# Sheet2.net
KiCad netlist of a schematic drawn in Altium Designer
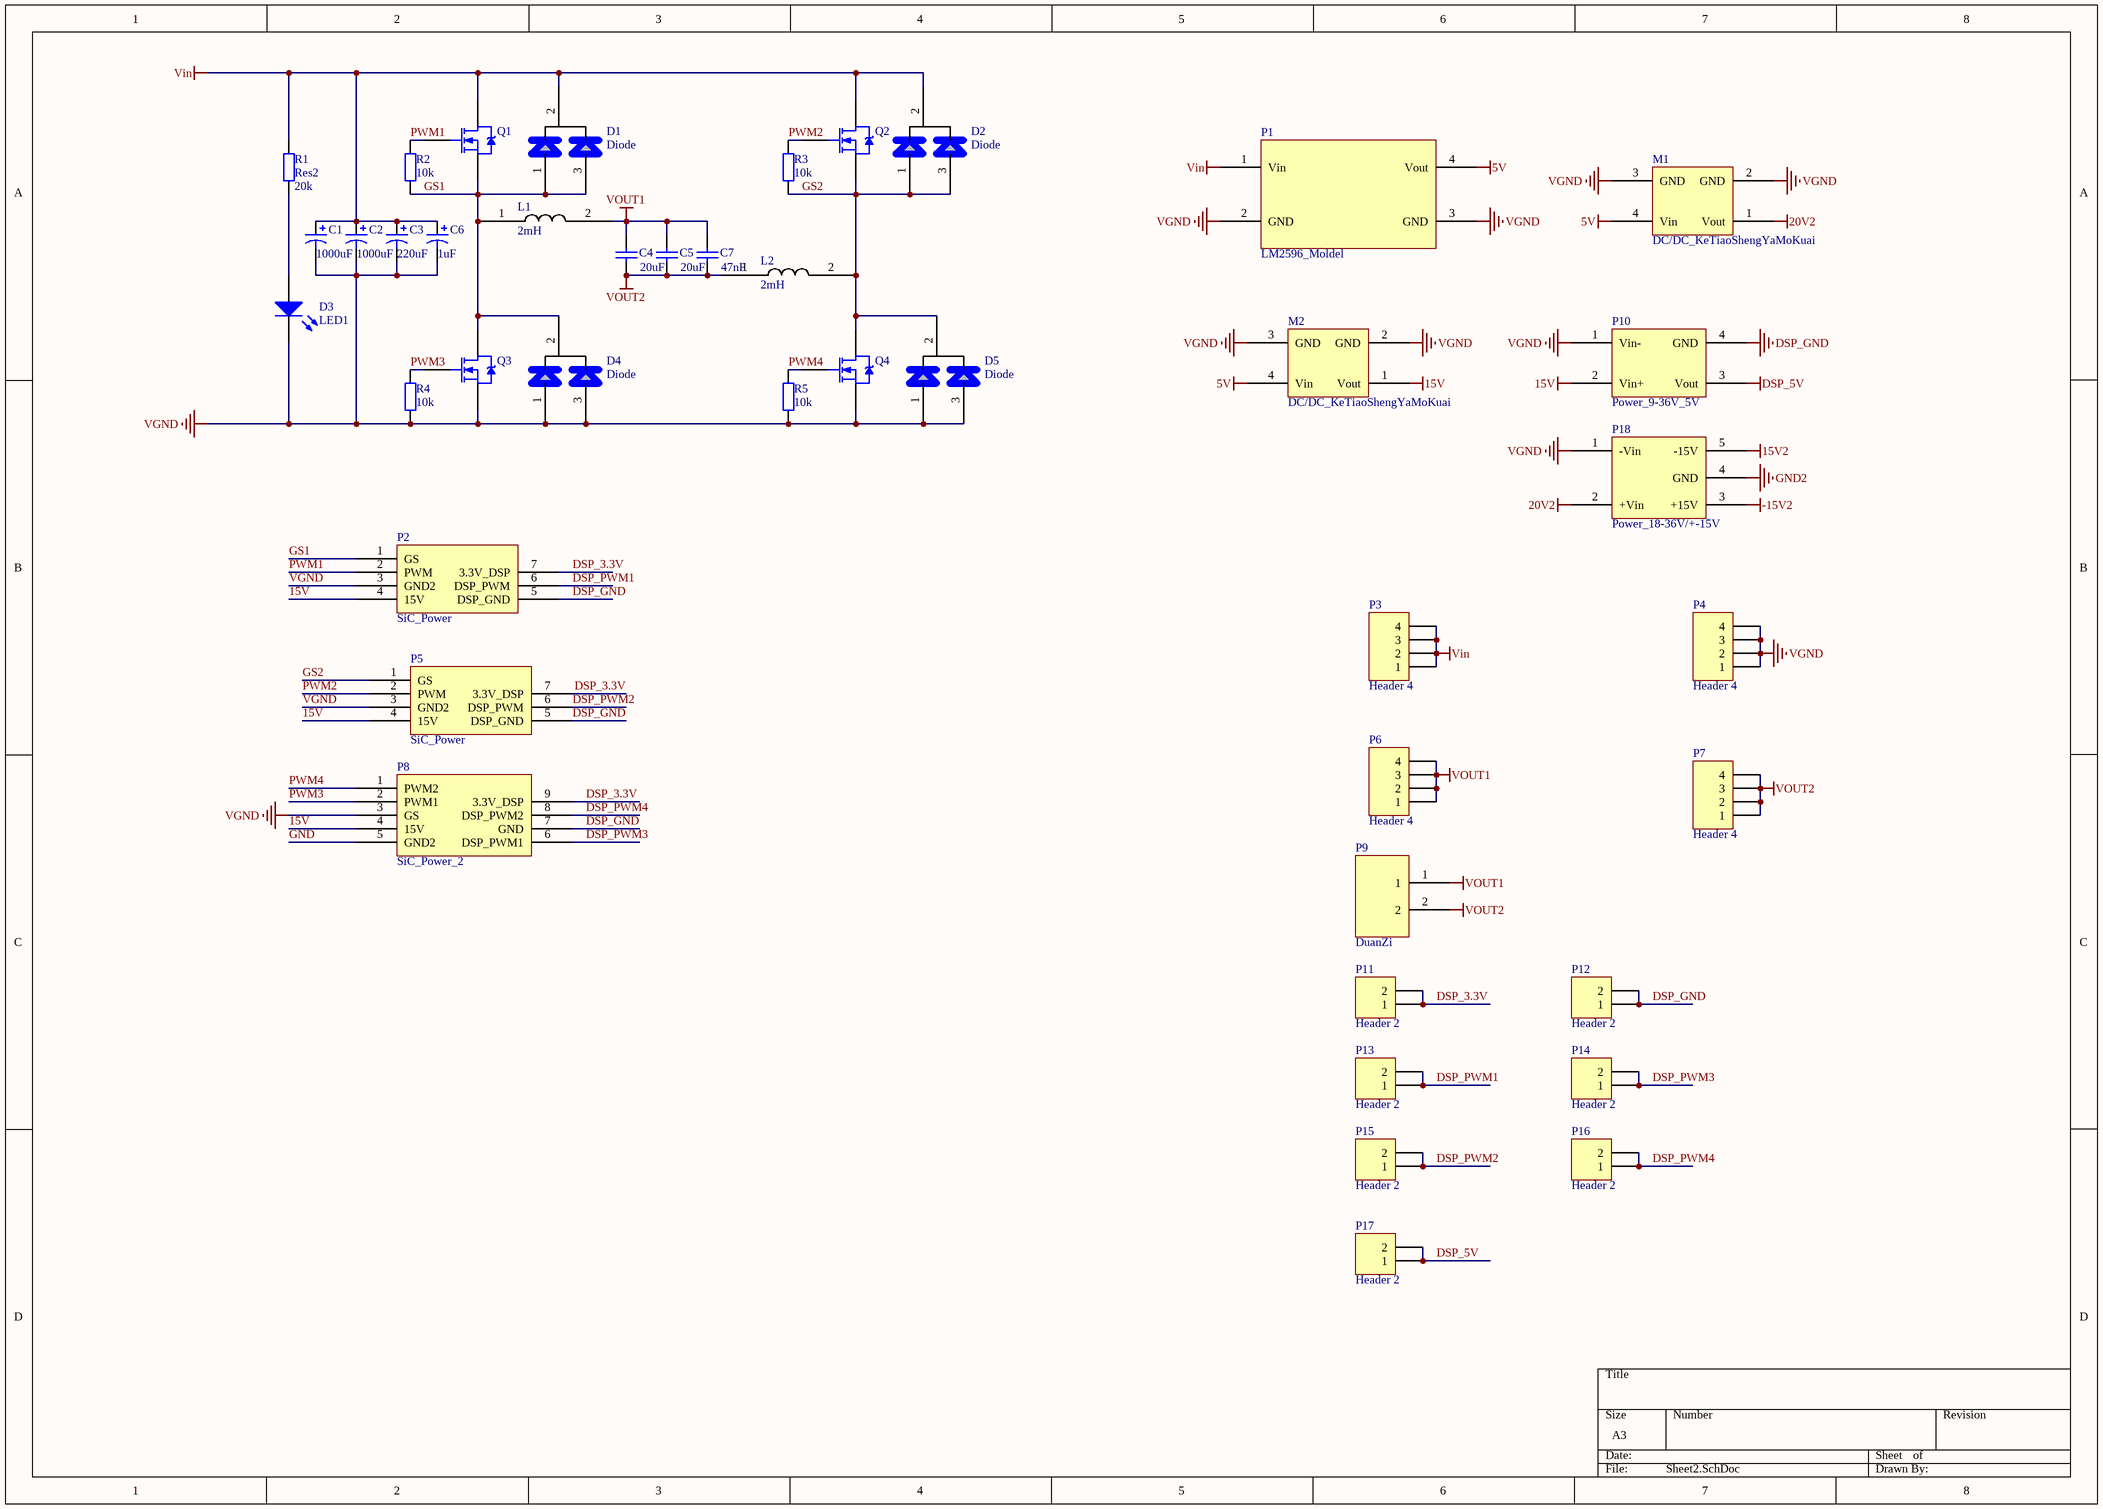
[diagram p0: Sheet2.SchDoc]

(export (version "E")
  (design (tool "Eeschema 10.0.6"))
  (components
    (comp (ref "C1")
      (value "1000uF")
      (footprint "C_1000uF_220uF")
      (description "Polarized Capacitor (Radial)")
      (fields (field (name "Comment") "Cap Pol1") (field (name "PUBLISHER") "Altium Limited"))
      (libsource (lib "Miscellaneous Devices") (part "Cap Pol1"))
    )
    (comp (ref "C2")
      (value "1000uF")
      (footprint "C_1000uF_220uF")
      (description "Polarized Capacitor (Radial)")
      (fields (field (name "Comment") "Cap Pol1") (field (name "PUBLISHER") "Altium Limited"))
      (libsource (lib "Miscellaneous Devices") (part "Cap Pol1"))
    )
    (comp (ref "C3")
      (value "220uF")
      (footprint "C_1000uF_220uF")
      (description "Polarized Capacitor (Radial)")
      (fields (field (name "Comment") "Cap Pol1") (field (name "PUBLISHER") "Altium Limited"))
      (libsource (lib "Miscellaneous Devices") (part "Cap Pol1"))
    )
    (comp (ref "C4")
      (value "20uF")
      (footprint "C_20uF_BaoMo")
      (description "Capacitor (Semiconductor SIM Model)")
      (fields (field (name "Comment") "Cap Semi") (field (name "PUBLISHER") "Altium Limited"))
      (libsource (lib "Miscellaneous Devices") (part "Cap Semi"))
    )
    (comp (ref "C5")
      (value "20uF")
      (footprint "C_20uF_BaoMo")
      (description "Capacitor (Semiconductor SIM Model)")
      (fields (field (name "Comment") "Cap Semi") (field (name "PUBLISHER") "Altium Limited"))
      (libsource (lib "Miscellaneous Devices") (part "Cap Semi"))
    )
    (comp (ref "C6")
      (value "1uF")
      (footprint "C_MKP_1uF")
      (description "Polarized Capacitor (Radial)")
      (fields (field (name "Comment") "Cap Pol1") (field (name "PUBLISHER") "Altium Limited"))
      (libsource (lib "Miscellaneous Devices") (part "Cap Pol1"))
    )
    (comp (ref "C7")
      (value "47nF")
      (footprint "C_0047_630_400_47nF")
      (description "Capacitor (Semiconductor SIM Model)")
      (fields (field (name "Comment") "Cap Semi") (field (name "PUBLISHER") "Altium Limited"))
      (libsource (lib "Miscellaneous Devices") (part "Cap Semi"))
    )
    (comp (ref "D1") (value "Diode") (footprint "SiC-MOS") (libsource (lib "sharing") (part "Diode")))
    (comp (ref "D2") (value "Diode") (footprint "SiC-MOS") (libsource (lib "sharing") (part "Diode")))
    (comp (ref "D3")
      (value "LED1")
      (footprint "LED")
      (description "Typical RED GaAs LED")
      (fields (field (name "PUBLISHER") "Altium Limited"))
      (libsource (lib "Miscellaneous Devices") (part "LED1"))
    )
    (comp (ref "D4") (value "Diode") (footprint "SiC-MOS") (libsource (lib "sharing") (part "Diode")))
    (comp (ref "D5") (value "Diode") (footprint "SiC-MOS") (libsource (lib "sharing") (part "Diode")))
    (comp (ref "L1") (value "2mH") (footprint "L_2mH") (libsource (lib "sharing") (part "L")))
    (comp (ref "L2") (value "2mH") (footprint "L_2mH") (libsource (lib "sharing") (part "L")))
    (comp (ref "M1")
      (value "DC/DC_KeTiaoShengYaMoKuai")
      (footprint "DC/DC-KeTiaoShengYaMoBan")
      (libsource (lib "sharing") (part "DC/DC_KeTiaoShengYaMoKuai"))
    )
    (comp (ref "M2")
      (value "DC/DC_KeTiaoShengYaMoKuai")
      (footprint "DC/DC-KeTiaoShengYaMoBan")
      (libsource (lib "sharing") (part "DC/DC_KeTiaoShengYaMoKuai"))
    )
    (comp (ref "P1")
      (value "LM2596_Moldel")
      (footprint "LM2596_Moldel")
      (libsource (lib "sharing") (part "LM2596_Moldel"))
    )
    (comp (ref "P2")
      (value "SiC_Power")
      (footprint "SiC_Power")
      (libsource (lib "sharing") (part "SiC_Power"))
    )
    (comp (ref "P3")
      (value "Header 4")
      (footprint "HDR1X4")
      (description "Header, 4-Pin")
      (fields (field (name "PUBLISHER") "Altium Limited"))
      (libsource (lib "Miscellaneous Connectors") (part "Header 4"))
    )
    (comp (ref "P4")
      (value "Header 4")
      (footprint "HDR1X4")
      (description "Header, 4-Pin")
      (fields (field (name "PUBLISHER") "Altium Limited"))
      (libsource (lib "Miscellaneous Connectors") (part "Header 4"))
    )
    (comp (ref "P5")
      (value "SiC_Power")
      (footprint "SiC_Power")
      (libsource (lib "sharing") (part "SiC_Power"))
    )
    (comp (ref "P6")
      (value "Header 4")
      (footprint "HDR1X4")
      (description "Header, 4-Pin")
      (fields (field (name "PUBLISHER") "Altium Limited"))
      (libsource (lib "Miscellaneous Connectors") (part "Header 4"))
    )
    (comp (ref "P7")
      (value "Header 4")
      (footprint "HDR1X4")
      (description "Header, 4-Pin")
      (fields (field (name "PUBLISHER") "Altium Limited"))
      (libsource (lib "Miscellaneous Connectors") (part "Header 4"))
    )
    (comp (ref "P8")
      (value "SiC_Power_2")
      (footprint "SiC_Power_2")
      (libsource (lib "sharing") (part "SiC_Power_2"))
    )
    (comp (ref "P9")
      (value "DuanZi")
      (footprint "DuanZi")
      (libsource (lib "sharing_Library1") (part "DuanZi"))
    )
    (comp (ref "P10")
      (value "Power_9-36V_5V")
      (footprint "Power_9-36V/5V")
      (libsource (lib "sharing") (part "Power_9-36V_5V"))
    )
    (comp (ref "P11")
      (value "Header 2")
      (footprint "HDR1X2")
      (description "Header, 2-Pin")
      (fields (field (name "PUBLISHER") "Altium Limited"))
      (libsource (lib "Miscellaneous Connectors") (part "Header 2"))
    )
    (comp (ref "P12")
      (value "Header 2")
      (footprint "HDR1X2")
      (description "Header, 2-Pin")
      (fields (field (name "PUBLISHER") "Altium Limited"))
      (libsource (lib "Miscellaneous Connectors") (part "Header 2"))
    )
    (comp (ref "P13")
      (value "Header 2")
      (footprint "HDR1X2")
      (description "Header, 2-Pin")
      (fields (field (name "PUBLISHER") "Altium Limited"))
      (libsource (lib "Miscellaneous Connectors") (part "Header 2"))
    )
    (comp (ref "P14")
      (value "Header 2")
      (footprint "HDR1X2")
      (description "Header, 2-Pin")
      (fields (field (name "PUBLISHER") "Altium Limited"))
      (libsource (lib "Miscellaneous Connectors") (part "Header 2"))
    )
    (comp (ref "P15")
      (value "Header 2")
      (footprint "HDR1X2")
      (description "Header, 2-Pin")
      (fields (field (name "PUBLISHER") "Altium Limited"))
      (libsource (lib "Miscellaneous Connectors") (part "Header 2"))
    )
    (comp (ref "P16")
      (value "Header 2")
      (footprint "HDR1X2")
      (description "Header, 2-Pin")
      (fields (field (name "PUBLISHER") "Altium Limited"))
      (libsource (lib "Miscellaneous Connectors") (part "Header 2"))
    )
    (comp (ref "P17")
      (value "Header 2")
      (footprint "HDR1X2")
      (description "Header, 2-Pin")
      (fields (field (name "PUBLISHER") "Altium Limited"))
      (libsource (lib "Miscellaneous Connectors") (part "Header 2"))
    )
    (comp (ref "P18")
      (value "Power_18-36V/+-15V")
      (footprint "Power_18-36V/-+15V")
      (libsource (lib "sharing") (part "Power_18-36V/+-15V"))
    )
    (comp (ref "Q1")
      (value "NMOS-2")
      (footprint "SiC-MOS")
      (description "N-Channel Power MOSFET")
      (fields (field (name "PUBLISHER") "Altium Limited"))
      (libsource (lib "Miscellaneous Devices") (part "NMOS-2"))
    )
    (comp (ref "Q2")
      (value "NMOS-2")
      (footprint "SiC-MOS")
      (description "N-Channel Power MOSFET")
      (fields (field (name "PUBLISHER") "Altium Limited"))
      (libsource (lib "Miscellaneous Devices") (part "NMOS-2"))
    )
    (comp (ref "Q3")
      (value "NMOS-2")
      (footprint "SiC-MOS")
      (description "N-Channel Power MOSFET")
      (fields (field (name "PUBLISHER") "Altium Limited"))
      (libsource (lib "Miscellaneous Devices") (part "NMOS-2"))
    )
    (comp (ref "Q4")
      (value "NMOS-2")
      (footprint "SiC-MOS")
      (description "N-Channel Power MOSFET")
      (fields (field (name "PUBLISHER") "Altium Limited"))
      (libsource (lib "Miscellaneous Devices") (part "NMOS-2"))
    )
    (comp (ref "R1")
      (value "Res2")
      (footprint "R")
      (description "Resistor")
      (fields (field (name "ALTIUM_VALUE") "20k") (field (name "PUBLISHER") "Altium Limited"))
      (libsource (lib "") (part "Res2_1"))
    )
    (comp (ref "R2")
      (value "10k")
      (footprint "AXIAL-0.4")
      (description "Resistor")
      (fields (field (name "Comment") "Res2") (field (name "PUBLISHER") "Altium Limited"))
      (libsource (lib "Miscellaneous Devices") (part "Res2"))
    )
    (comp (ref "R3")
      (value "10k")
      (footprint "AXIAL-0.4")
      (description "Resistor")
      (fields (field (name "Comment") "Res2") (field (name "PUBLISHER") "Altium Limited"))
      (libsource (lib "Miscellaneous Devices") (part "Res2"))
    )
    (comp (ref "R4")
      (value "10k")
      (footprint "AXIAL-0.4")
      (description "Resistor")
      (fields (field (name "Comment") "Res2") (field (name "PUBLISHER") "Altium Limited"))
      (libsource (lib "Miscellaneous Devices") (part "Res2"))
    )
    (comp (ref "R5")
      (value "10k")
      (footprint "AXIAL-0.4")
      (description "Resistor")
      (fields (field (name "Comment") "Res2") (field (name "PUBLISHER") "Altium Limited"))
      (libsource (lib "Miscellaneous Devices") (part "Res2"))
    )
  )
  (nets
    (net (code "1") (name "-15V2") (class "Default")
      (node (ref "P18") (pin "3") (pinfunction "+15V_3") (pintype "passive"))
    )
    (net (code "2") (name "/DSP_3.3V") (class "Default")
      (node (ref "P11") (pin "1") (pinfunction "1_1") (pintype "passive"))
      (node (ref "P11") (pin "2") (pinfunction "2_2") (pintype "passive"))
      (node (ref "P2") (pin "7") (pinfunction "3.3V_DSP_7") (pintype "passive"))
      (node (ref "P5") (pin "7") (pinfunction "3.3V_DSP_7") (pintype "passive"))
      (node (ref "P8") (pin "9") (pinfunction "3.3V_DSP_9") (pintype "passive"))
    )
    (net (code "3") (name "/DSP_PWM1") (class "Default")
      (node (ref "P13") (pin "1") (pinfunction "1_1") (pintype "passive"))
      (node (ref "P13") (pin "2") (pinfunction "2_2") (pintype "passive"))
      (node (ref "P2") (pin "6") (pinfunction "DSP_PWM_6") (pintype "passive"))
    )
    (net (code "4") (name "/DSP_PWM2") (class "Default")
      (node (ref "P15") (pin "1") (pinfunction "1_1") (pintype "passive"))
      (node (ref "P15") (pin "2") (pinfunction "2_2") (pintype "passive"))
      (node (ref "P5") (pin "6") (pinfunction "DSP_PWM_6") (pintype "passive"))
    )
    (net (code "5") (name "/DSP_PWM3") (class "Default")
      (node (ref "P14") (pin "1") (pinfunction "1_1") (pintype "passive"))
      (node (ref "P14") (pin "2") (pinfunction "2_2") (pintype "passive"))
      (node (ref "P8") (pin "6") (pinfunction "DSP_PWM1_6") (pintype "passive"))
    )
    (net (code "6") (name "/DSP_PWM4") (class "Default")
      (node (ref "P16") (pin "1") (pinfunction "1_1") (pintype "passive"))
      (node (ref "P16") (pin "2") (pinfunction "2_2") (pintype "passive"))
      (node (ref "P8") (pin "8") (pinfunction "DSP_PWM2_8") (pintype "passive"))
    )
    (net (code "7") (name "/GND") (class "Default")
      (node (ref "P8") (pin "5") (pinfunction "GND2_5") (pintype "passive"))
    )
    (net (code "8") (name "/GS1") (class "Default")
      (node (ref "D1") (pin "1") (pinfunction "1_1") (pintype "passive"))
      (node (ref "D1") (pin "3") (pinfunction "3_3") (pintype "passive"))
      (node (ref "D4") (pin "2") (pinfunction "2_2") (pintype "passive"))
      (node (ref "L1") (pin "1") (pinfunction "1_1") (pintype "passive"))
      (node (ref "P2") (pin "1") (pinfunction "GS_1") (pintype "passive"))
      (node (ref "Q1") (pin "3") (pinfunction "S_3") (pintype "passive"))
      (node (ref "Q3") (pin "2") (pinfunction "D_2") (pintype "passive"))
      (node (ref "R2") (pin "1") (pinfunction "1_1") (pintype "passive"))
    )
    (net (code "9") (name "/GS2") (class "Default")
      (node (ref "D2") (pin "1") (pinfunction "1_1") (pintype "passive"))
      (node (ref "D2") (pin "3") (pinfunction "3_3") (pintype "passive"))
      (node (ref "D5") (pin "2") (pinfunction "2_2") (pintype "passive"))
      (node (ref "L2") (pin "2") (pinfunction "2_2") (pintype "passive"))
      (node (ref "P5") (pin "1") (pinfunction "GS_1") (pintype "passive"))
      (node (ref "Q2") (pin "3") (pinfunction "S_3") (pintype "passive"))
      (node (ref "Q4") (pin "2") (pinfunction "D_2") (pintype "passive"))
      (node (ref "R3") (pin "1") (pinfunction "1_1") (pintype "passive"))
    )
    (net (code "10") (name "/PWM1") (class "Default")
      (node (ref "P2") (pin "2") (pinfunction "PWM_2") (pintype "passive"))
      (node (ref "Q1") (pin "1") (pinfunction "G_1") (pintype "passive"))
      (node (ref "R2") (pin "2") (pinfunction "2_2") (pintype "passive"))
    )
    (net (code "11") (name "/PWM2") (class "Default")
      (node (ref "P5") (pin "2") (pinfunction "PWM_2") (pintype "passive"))
      (node (ref "Q2") (pin "1") (pinfunction "G_1") (pintype "passive"))
      (node (ref "R3") (pin "2") (pinfunction "2_2") (pintype "passive"))
    )
    (net (code "12") (name "/PWM3") (class "Default")
      (node (ref "P8") (pin "2") (pinfunction "PWM1_2") (pintype "passive"))
      (node (ref "Q3") (pin "1") (pinfunction "G_1") (pintype "passive"))
      (node (ref "R4") (pin "2") (pinfunction "2_2") (pintype "passive"))
    )
    (net (code "13") (name "/PWM4") (class "Default")
      (node (ref "P8") (pin "1") (pinfunction "PWM2_1") (pintype "passive"))
      (node (ref "Q4") (pin "1") (pinfunction "G_1") (pintype "passive"))
      (node (ref "R5") (pin "2") (pinfunction "2_2") (pintype "passive"))
    )
    (net (code "14") (name "5V") (class "Default")
      (node (ref "M1") (pin "4") (pinfunction "Vin_4") (pintype "passive"))
      (node (ref "M2") (pin "4") (pinfunction "Vin_4") (pintype "passive"))
      (node (ref "P1") (pin "4") (pinfunction "Vout_4") (pintype "passive"))
    )
    (net (code "15") (name "15V") (class "Default")
      (node (ref "M2") (pin "1") (pinfunction "Vout_1") (pintype "passive"))
      (node (ref "P10") (pin "2") (pinfunction "Vin+_2") (pintype "passive"))
      (node (ref "P2") (pin "4") (pinfunction "15V_4") (pintype "passive"))
      (node (ref "P5") (pin "4") (pinfunction "15V_4") (pintype "passive"))
      (node (ref "P8") (pin "4") (pinfunction "15V_4") (pintype "passive"))
    )
    (net (code "16") (name "15V2") (class "Default")
      (node (ref "P18") (pin "5") (pinfunction "-15V_5") (pintype "passive"))
    )
    (net (code "17") (name "20V2") (class "Default")
      (node (ref "M1") (pin "1") (pinfunction "Vout_1") (pintype "passive"))
      (node (ref "P18") (pin "2") (pinfunction "+Vin_2") (pintype "passive"))
    )
    (net (code "18") (name "DSP_5V") (class "Default")
      (node (ref "P10") (pin "3") (pinfunction "Vout_3") (pintype "passive"))
      (node (ref "P17") (pin "1") (pinfunction "1_1") (pintype "passive"))
      (node (ref "P17") (pin "2") (pinfunction "2_2") (pintype "passive"))
    )
    (net (code "19") (name "DSP_GND") (class "Default")
      (node (ref "P10") (pin "4") (pinfunction "GND_4") (pintype "passive"))
      (node (ref "P12") (pin "1") (pinfunction "1_1") (pintype "passive"))
      (node (ref "P12") (pin "2") (pinfunction "2_2") (pintype "passive"))
      (node (ref "P2") (pin "5") (pinfunction "DSP_GND_5") (pintype "passive"))
      (node (ref "P5") (pin "5") (pinfunction "DSP_GND_5") (pintype "passive"))
      (node (ref "P8") (pin "7") (pinfunction "GND_7") (pintype "passive"))
    )
    (net (code "20") (name "GND2") (class "Default")
      (node (ref "P18") (pin "4") (pinfunction "GND_4") (pintype "passive"))
    )
    (net (code "21") (name "Net-(D3-A)") (class "Default")
      (node (ref "D3") (pin "1") (pinfunction "A_1") (pintype "passive"))
      (node (ref "R1") (pin "2") (pinfunction "2_2") (pintype "passive"))
    )
    (net (code "22") (name "VGND") (class "Default")
      (node (ref "C1") (pin "2") (pinfunction "2_2") (pintype "passive"))
      (node (ref "C2") (pin "2") (pinfunction "2_2") (pintype "passive"))
      (node (ref "C3") (pin "2") (pinfunction "2_2") (pintype "passive"))
      (node (ref "C6") (pin "2") (pinfunction "2_2") (pintype "passive"))
      (node (ref "D3") (pin "2") (pinfunction "K_2") (pintype "passive"))
      (node (ref "D4") (pin "1") (pinfunction "1_1") (pintype "passive"))
      (node (ref "D4") (pin "3") (pinfunction "3_3") (pintype "passive"))
      (node (ref "D5") (pin "1") (pinfunction "1_1") (pintype "passive"))
      (node (ref "D5") (pin "3") (pinfunction "3_3") (pintype "passive"))
      (node (ref "M1") (pin "2") (pinfunction "GND_2") (pintype "passive"))
      (node (ref "M1") (pin "3") (pinfunction "GND_3") (pintype "passive"))
      (node (ref "M2") (pin "2") (pinfunction "GND_2") (pintype "passive"))
      (node (ref "M2") (pin "3") (pinfunction "GND_3") (pintype "passive"))
      (node (ref "P1") (pin "2") (pinfunction "GND_2") (pintype "passive"))
      (node (ref "P1") (pin "3") (pinfunction "GND_3") (pintype "passive"))
      (node (ref "P10") (pin "1") (pinfunction "Vin-_1") (pintype "passive"))
      (node (ref "P18") (pin "1") (pinfunction "-Vin_1") (pintype "passive"))
      (node (ref "P2") (pin "3") (pinfunction "GND2_3") (pintype "passive"))
      (node (ref "P4") (pin "1") (pinfunction "1_1") (pintype "passive"))
      (node (ref "P4") (pin "2") (pinfunction "2_2") (pintype "passive"))
      (node (ref "P4") (pin "3") (pinfunction "3_3") (pintype "passive"))
      (node (ref "P4") (pin "4") (pinfunction "4_4") (pintype "passive"))
      (node (ref "P5") (pin "3") (pinfunction "GND2_3") (pintype "passive"))
      (node (ref "P8") (pin "3") (pinfunction "GS_3") (pintype "passive"))
      (node (ref "Q3") (pin "3") (pinfunction "S_3") (pintype "passive"))
      (node (ref "Q4") (pin "3") (pinfunction "S_3") (pintype "passive"))
      (node (ref "R4") (pin "1") (pinfunction "1_1") (pintype "passive"))
      (node (ref "R5") (pin "1") (pinfunction "1_1") (pintype "passive"))
    )
    (net (code "23") (name "VOUT1") (class "Default")
      (node (ref "C4") (pin "2") (pinfunction "2_2") (pintype "passive"))
      (node (ref "C5") (pin "2") (pinfunction "2_2") (pintype "passive"))
      (node (ref "C7") (pin "2") (pinfunction "2_2") (pintype "passive"))
      (node (ref "L1") (pin "2") (pinfunction "2_2") (pintype "passive"))
      (node (ref "P6") (pin "1") (pinfunction "1_1") (pintype "passive"))
      (node (ref "P6") (pin "2") (pinfunction "2_2") (pintype "passive"))
      (node (ref "P6") (pin "3") (pinfunction "3_3") (pintype "passive"))
      (node (ref "P6") (pin "4") (pinfunction "4_4") (pintype "passive"))
      (node (ref "P9") (pin "1") (pinfunction "1_1") (pintype "passive"))
    )
    (net (code "24") (name "VOUT2") (class "Default")
      (node (ref "C4") (pin "1") (pinfunction "1_1") (pintype "passive"))
      (node (ref "C5") (pin "1") (pinfunction "1_1") (pintype "passive"))
      (node (ref "C7") (pin "1") (pinfunction "1_1") (pintype "passive"))
      (node (ref "L2") (pin "1") (pinfunction "1_1") (pintype "passive"))
      (node (ref "P7") (pin "1") (pinfunction "1_1") (pintype "passive"))
      (node (ref "P7") (pin "2") (pinfunction "2_2") (pintype "passive"))
      (node (ref "P7") (pin "3") (pinfunction "3_3") (pintype "passive"))
      (node (ref "P7") (pin "4") (pinfunction "4_4") (pintype "passive"))
      (node (ref "P9") (pin "2") (pinfunction "2_2") (pintype "passive"))
    )
    (net (code "25") (name "Vin") (class "Default")
      (node (ref "C1") (pin "1") (pinfunction "1_1") (pintype "passive"))
      (node (ref "C2") (pin "1") (pinfunction "1_1") (pintype "passive"))
      (node (ref "C3") (pin "1") (pinfunction "1_1") (pintype "passive"))
      (node (ref "C6") (pin "1") (pinfunction "1_1") (pintype "passive"))
      (node (ref "D1") (pin "2") (pinfunction "2_2") (pintype "passive"))
      (node (ref "D2") (pin "2") (pinfunction "2_2") (pintype "passive"))
      (node (ref "P1") (pin "1") (pinfunction "Vin_1") (pintype "passive"))
      (node (ref "P3") (pin "1") (pinfunction "1_1") (pintype "passive"))
      (node (ref "P3") (pin "2") (pinfunction "2_2") (pintype "passive"))
      (node (ref "P3") (pin "3") (pinfunction "3_3") (pintype "passive"))
      (node (ref "P3") (pin "4") (pinfunction "4_4") (pintype "passive"))
      (node (ref "Q1") (pin "2") (pinfunction "D_2") (pintype "passive"))
      (node (ref "Q2") (pin "2") (pinfunction "D_2") (pintype "passive"))
      (node (ref "R1") (pin "1") (pinfunction "1_1") (pintype "passive"))
    )
  )
)
